# Par_Acondicionation.net
KiCad netlist of a schematic drawn in Altium Designer
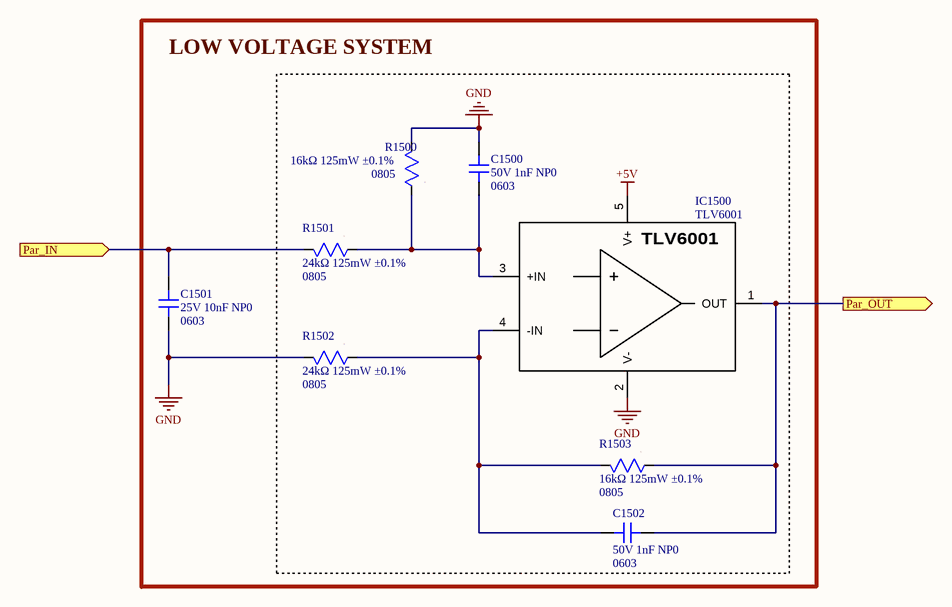
[diagram p0: Par_Acondicionation.SchDoc]

(export (version "E")
  (design (tool "Eeschema 10.0.6"))
  (components
    (comp (ref "C1500")
      (value "50V 1nF NP0")
      (footprint "CAP SMD 0603")
      (description "Condensadores de cerámica multicapa (MLCC- SMD/SMT) WCAP-CSGP 1000pF 0603 5% 50V MLCC")
      (fields
        (field (name "PACKAGE") "0603")
        (field (name "MPN") "885012006063")
        (field (name "MANUFACTURER") "Wurth Elektronik")
      )
      (libsource (lib "eUSR_Database") (part "CAP non polarized"))
    )
    (comp (ref "C1501")
      (value "25V 10nF NP0")
      (footprint "CAP SMD 0603")
      (description "Condensadores de cerámica multicapa (MLCC- SMD/SMT) 0.01 uF 25 VDC 1% 0603 C0G (NP0) AEC-Q200")
      (fields
        (field (name "PACKAGE") "0603")
        (field (name "MPN") "GRT1885C1E103FA02D")
        (field (name "MANUFACTURER") "muRata")
      )
      (libsource (lib "eUSR_Database") (part "CAP non polarized"))
    )
    (comp (ref "C1502")
      (value "50V 1nF NP0")
      (footprint "CAP SMD 0603")
      (description "Condensadores de cerámica multicapa (MLCC- SMD/SMT) WCAP-CSGP 1000pF 0603 5% 50V MLCC")
      (fields
        (field (name "PACKAGE") "0603")
        (field (name "MPN") "885012006063")
        (field (name "MANUFACTURER") "Wurth Elektronik")
      )
      (libsource (lib "eUSR_Database") (part "CAP non polarized"))
    )
    (comp (ref "IC1500")
      (value "TLV6001")
      (footprint "SOT-23-5")
      (fields (field (name "MPN") "TLV6001UIDBVR") (field (name "MANUFACTURER") "Texas Instruments"))
      (libsource (lib "eUSR_Database") (part "TLV6001"))
    )
    (comp (ref "R1500")
      (value "16kΩ 125mW ±0.1%")
      (footprint "RES SMD 0805")
      (description "Resistores de película fina - SMD 0805 16Kohm 0.1% 10ppm AEC-Q200")
      (fields
        (field (name "PACKAGE") "0805")
        (field (name "MPN") "ERA-6ARB163V")
        (field (name "MANUFACTURER") "Panasonic")
      )
      (libsource (lib "eUSR_Database") (part "RES"))
    )
    (comp (ref "R1501")
      (value "24kΩ 125mW ±0.1%")
      (footprint "RES SMD 0805")
      (description "Resistores de película fina - SMD 0805 24Kohm 0.1% 15ppm AEC-Q200")
      (fields
        (field (name "PACKAGE") "0805")
        (field (name "MPN") "ERA-6APB243V")
        (field (name "MANUFACTURER") "Panasonic")
      )
      (libsource (lib "eUSR_Database") (part "RES"))
    )
    (comp (ref "R1502")
      (value "24kΩ 125mW ±0.1%")
      (footprint "RES SMD 0805")
      (description "Resistores de película fina - SMD 0805 24Kohm 0.1% 15ppm AEC-Q200")
      (fields
        (field (name "PACKAGE") "0805")
        (field (name "MPN") "ERA-6APB243V")
        (field (name "MANUFACTURER") "Panasonic")
      )
      (libsource (lib "eUSR_Database") (part "RES"))
    )
    (comp (ref "R1503")
      (value "16kΩ 125mW ±0.1%")
      (footprint "RES SMD 0805")
      (description "Resistores de película fina - SMD 0805 16Kohm 0.1% 10ppm AEC-Q200")
      (fields
        (field (name "PACKAGE") "0805")
        (field (name "MPN") "ERA-6ARB163V")
        (field (name "MANUFACTURER") "Panasonic")
      )
      (libsource (lib "eUSR_Database") (part "RES"))
    )
  )
  (nets
    (net (code "1") (name "+5V") (class "Default")
      (node (ref "IC1500") (pin "5") (pinfunction "V+_5") (pintype "passive"))
    )
    (net (code "2") (name "/Par_IN") (class "Default")
      (node (ref "C1501") (pin "1") (pinfunction "1_1") (pintype "passive"))
      (node (ref "R1501") (pin "2") (pinfunction "2_2") (pintype "passive"))
    )
    (net (code "3") (name "/Par_OUT") (class "Default")
      (node (ref "C1502") (pin "2") (pinfunction "2_2") (pintype "passive"))
      (node (ref "IC1500") (pin "1") (pinfunction "OUT_1") (pintype "passive"))
      (node (ref "R1503") (pin "1") (pinfunction "1_1") (pintype "passive"))
    )
    (net (code "4") (name "GND") (class "Default")
      (node (ref "C1500") (pin "1") (pinfunction "1_1") (pintype "passive"))
      (node (ref "C1501") (pin "2") (pinfunction "2_2") (pintype "passive"))
      (node (ref "IC1500") (pin "2") (pinfunction "V-_2") (pintype "passive"))
      (node (ref "R1500") (pin "2") (pinfunction "2_2") (pintype "passive"))
      (node (ref "R1502") (pin "2") (pinfunction "2_2") (pintype "passive"))
    )
    (net (code "5") (name "Net-(IC1500-+IN)") (class "Default")
      (node (ref "C1500") (pin "2") (pinfunction "2_2") (pintype "passive"))
      (node (ref "IC1500") (pin "3") (pinfunction "+IN_3") (pintype "passive"))
      (node (ref "R1500") (pin "1") (pinfunction "1_1") (pintype "passive"))
      (node (ref "R1501") (pin "1") (pinfunction "1_1") (pintype "passive"))
    )
    (net (code "6") (name "Net-(IC1500--IN)") (class "Default")
      (node (ref "C1502") (pin "1") (pinfunction "1_1") (pintype "passive"))
      (node (ref "IC1500") (pin "4") (pinfunction "-IN_4") (pintype "passive"))
      (node (ref "R1502") (pin "1") (pinfunction "1_1") (pintype "passive"))
      (node (ref "R1503") (pin "2") (pinfunction "2_2") (pintype "passive"))
    )
  )
)
